# Driver_control.net
KiCad netlist of a schematic drawn in EAGLE
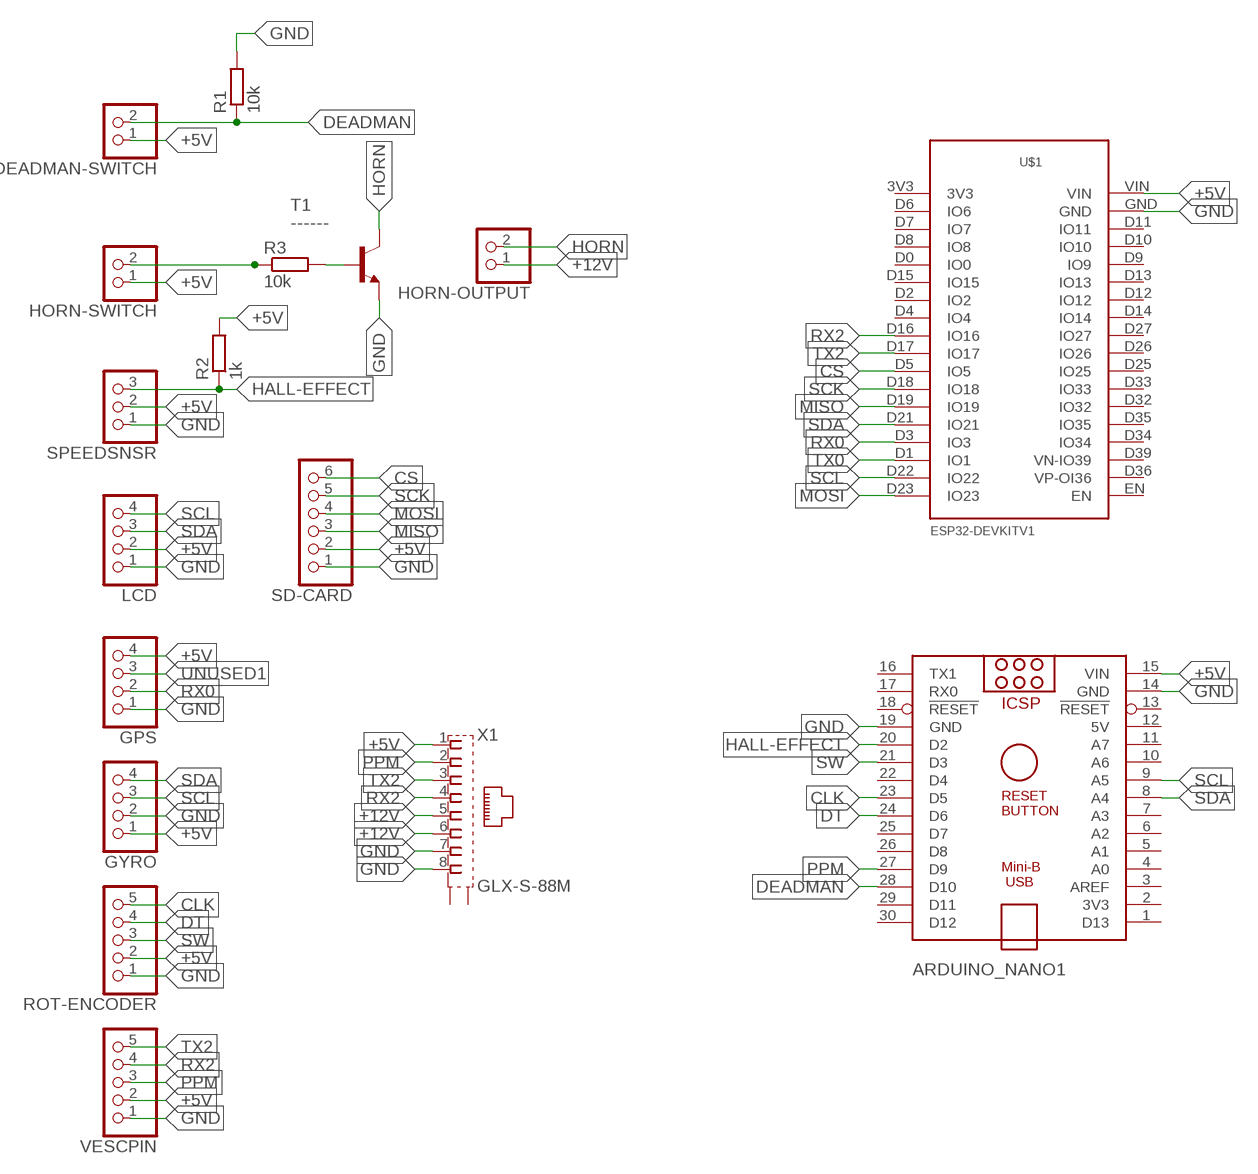
[diagram p0: schematic, sheet 1]

(export (version "E")
  (design (tool "Eeschema 10.0.6"))
  (components
    (comp (ref "ARDUINO_NANO1")
      (value "ARDUINO_NANO")
      (footprint "eagle-import:ARDUINO_NANO")
      (libsource (lib "eagle-import") (part "ARDUINO_NANO"))
    )
    (comp (ref "DEADMAN-SWITCH")
      (value "PINHD-1X2")
      (footprint "eagle-import:1X02")
      (libsource (lib "eagle-import") (part "PINHD-1X2"))
    )
    (comp (ref "GPS")
      (value "PINHD-1X4")
      (footprint "eagle-import:1X04")
      (libsource (lib "eagle-import") (part "PINHD-1X4"))
    )
    (comp (ref "GYRO")
      (value "PINHD-1X4")
      (footprint "eagle-import:1X04")
      (libsource (lib "eagle-import") (part "PINHD-1X4"))
    )
    (comp (ref "HORN-OUTPUT")
      (value "PINHD-1X2")
      (footprint "eagle-import:1X02")
      (libsource (lib "eagle-import") (part "PINHD-1X2"))
    )
    (comp (ref "HORN-SWITCH")
      (value "PINHD-1X2")
      (footprint "eagle-import:1X02")
      (libsource (lib "eagle-import") (part "PINHD-1X2"))
    )
    (comp (ref "LCD")
      (value "PINHD-1X4")
      (footprint "eagle-import:1X04")
      (libsource (lib "eagle-import") (part "PINHD-1X4"))
    )
    (comp (ref "R1")
      (value "10k")
      (footprint "eagle-import:0204_7")
      (libsource (lib "eagle-import") (part "R-EU_0204/7"))
    )
    (comp (ref "R2")
      (value "1k")
      (footprint "eagle-import:0204_7")
      (libsource (lib "eagle-import") (part "R-EU_0204/7"))
    )
    (comp (ref "R3")
      (value "10k")
      (footprint "eagle-import:0204_7")
      (libsource (lib "eagle-import") (part "R-EU_0204/7"))
    )
    (comp (ref "ROT-ENCODER")
      (value "PINHD-1X5")
      (footprint "eagle-import:1X05")
      (libsource (lib "eagle-import") (part "PINHD-1X5"))
    )
    (comp (ref "SD-CARD")
      (value "PINHD-1X6")
      (footprint "eagle-import:1X06")
      (libsource (lib "eagle-import") (part "PINHD-1X6"))
    )
    (comp (ref "SPEEDSNSR")
      (value "PINHD-1X3")
      (footprint "eagle-import:1X03")
      (libsource (lib "eagle-import") (part "PINHD-1X3"))
    )
    (comp (ref "T1")
      (value "------")
      (footprint "eagle-import:TO5")
      (libsource (lib "eagle-import") (part "2N2219"))
    )
    (comp (ref "U$1")
      (value "ESP32DEVKITV1")
      (footprint "eagle-import:ESP32-DEVKITV1")
      (libsource (lib "eagle-import") (part "ESP32DEVKITV1"))
    )
    (comp (ref "VESCPIN")
      (value "PINHD-1X5")
      (footprint "eagle-import:1X05")
      (libsource (lib "eagle-import") (part "PINHD-1X5"))
    )
    (comp (ref "X1")
      (value "GLX-S-88M")
      (footprint "eagle-import:GLX-S-88M")
      (libsource (lib "eagle-import") (part "GLX-S-88M"))
    )
  )
  (nets
    (net (code "1") (name "+5V") (class "Default")
      (node (ref "ARDUINO_NANO1") (pin "15") (pinfunction "VIN_15") (pintype "power_in"))
      (node (ref "DEADMAN-SWITCH") (pin "1") (pinfunction "1_1") (pintype "passive"))
      (node (ref "GPS") (pin "4") (pinfunction "4_4") (pintype "passive"))
      (node (ref "GYRO") (pin "1") (pinfunction "1_1") (pintype "passive"))
      (node (ref "HORN-SWITCH") (pin "1") (pinfunction "1_1") (pintype "passive"))
      (node (ref "LCD") (pin "2") (pinfunction "2_2") (pintype "passive"))
      (node (ref "R2") (pin "2") (pinfunction "2_2") (pintype "passive"))
      (node (ref "ROT-ENCODER") (pin "2") (pinfunction "2_2") (pintype "passive"))
      (node (ref "SD-CARD") (pin "2") (pinfunction "2_2") (pintype "passive"))
      (node (ref "SPEEDSNSR") (pin "2") (pinfunction "2_2") (pintype "passive"))
      (node (ref "U$1") (pin "VIN") (pinfunction "VIN_VIN") (pintype "bidirectional"))
      (node (ref "VESCPIN") (pin "2") (pinfunction "2_2") (pintype "passive"))
      (node (ref "X1") (pin "1") (pinfunction "1_1") (pintype "passive"))
    )
    (net (code "2") (name "+12V") (class "Default")
      (node (ref "HORN-OUTPUT") (pin "1") (pinfunction "1_1") (pintype "passive"))
      (node (ref "X1") (pin "5") (pinfunction "5_5") (pintype "passive"))
      (node (ref "X1") (pin "6") (pinfunction "6_6") (pintype "passive"))
    )
    (net (code "3") (name "/5V") (class "Default")
      (node (ref "ARDUINO_NANO1") (pin "12") (pinfunction "5V_12") (pintype "power_in"))
    )
    (net (code "4") (name "CLK") (class "Default")
      (node (ref "ARDUINO_NANO1") (pin "23") (pinfunction "D5_23") (pintype "bidirectional"))
      (node (ref "ROT-ENCODER") (pin "5") (pinfunction "5_5") (pintype "passive"))
    )
    (net (code "5") (name "CS") (class "Default")
      (node (ref "SD-CARD") (pin "6") (pinfunction "6_6") (pintype "passive"))
      (node (ref "U$1") (pin "D5") (pinfunction "IO5_D5") (pintype "bidirectional"))
    )
    (net (code "6") (name "DEADMAN") (class "Default")
      (node (ref "ARDUINO_NANO1") (pin "28") (pinfunction "D10_28") (pintype "bidirectional"))
      (node (ref "DEADMAN-SWITCH") (pin "2") (pinfunction "2_2") (pintype "passive"))
      (node (ref "R1") (pin "1") (pinfunction "1_1") (pintype "passive"))
    )
    (net (code "7") (name "DT") (class "Default")
      (node (ref "ARDUINO_NANO1") (pin "24") (pinfunction "D6_24") (pintype "bidirectional"))
      (node (ref "ROT-ENCODER") (pin "4") (pinfunction "4_4") (pintype "passive"))
    )
    (net (code "8") (name "GND") (class "Default")
      (node (ref "ARDUINO_NANO1") (pin "14") (pinfunction "GND_14") (pintype "power_in"))
      (node (ref "ARDUINO_NANO1") (pin "19") (pinfunction "GND_19") (pintype "power_in"))
      (node (ref "GPS") (pin "1") (pinfunction "1_1") (pintype "passive"))
      (node (ref "GYRO") (pin "2") (pinfunction "2_2") (pintype "passive"))
      (node (ref "LCD") (pin "1") (pinfunction "1_1") (pintype "passive"))
      (node (ref "R1") (pin "2") (pinfunction "2_2") (pintype "passive"))
      (node (ref "ROT-ENCODER") (pin "1") (pinfunction "1_1") (pintype "passive"))
      (node (ref "SD-CARD") (pin "1") (pinfunction "1_1") (pintype "passive"))
      (node (ref "SPEEDSNSR") (pin "1") (pinfunction "1_1") (pintype "passive"))
      (node (ref "T1") (pin "1") (pinfunction "E_1") (pintype "passive"))
      (node (ref "U$1") (pin "GND") (pinfunction "GND_GND") (pintype "bidirectional"))
      (node (ref "VESCPIN") (pin "1") (pinfunction "1_1") (pintype "passive"))
      (node (ref "X1") (pin "7") (pinfunction "7_7") (pintype "passive"))
      (node (ref "X1") (pin "8") (pinfunction "8_8") (pintype "passive"))
    )
    (net (code "9") (name "HALL-EFFECT") (class "Default")
      (node (ref "ARDUINO_NANO1") (pin "20") (pinfunction "D2_20") (pintype "bidirectional"))
      (node (ref "R2") (pin "1") (pinfunction "1_1") (pintype "passive"))
      (node (ref "SPEEDSNSR") (pin "3") (pinfunction "3_3") (pintype "passive"))
    )
    (net (code "10") (name "HORN") (class "Default")
      (node (ref "HORN-OUTPUT") (pin "2") (pinfunction "2_2") (pintype "passive"))
      (node (ref "T1") (pin "3") (pinfunction "C_3") (pintype "passive"))
    )
    (net (code "11") (name "MISO") (class "Default")
      (node (ref "SD-CARD") (pin "3") (pinfunction "3_3") (pintype "passive"))
      (node (ref "U$1") (pin "D19") (pinfunction "IO19_D19") (pintype "bidirectional"))
    )
    (net (code "12") (name "MOSI") (class "Default")
      (node (ref "SD-CARD") (pin "4") (pinfunction "4_4") (pintype "passive"))
      (node (ref "U$1") (pin "D23") (pinfunction "IO23_D23") (pintype "bidirectional"))
    )
    (net (code "13") (name "Net-(HORN-SWITCH-Pad2)") (class "Default")
      (node (ref "HORN-SWITCH") (pin "2") (pinfunction "2_2") (pintype "passive"))
      (node (ref "R3") (pin "1") (pinfunction "1_1") (pintype "passive"))
    )
    (net (code "14") (name "Net-(T1-B)") (class "Default")
      (node (ref "R3") (pin "2") (pinfunction "2_2") (pintype "passive"))
      (node (ref "T1") (pin "2") (pinfunction "B_2") (pintype "passive"))
    )
    (net (code "15") (name "PPM") (class "Default")
      (node (ref "ARDUINO_NANO1") (pin "27") (pinfunction "D9_27") (pintype "bidirectional"))
      (node (ref "VESCPIN") (pin "3") (pinfunction "3_3") (pintype "passive"))
      (node (ref "X1") (pin "2") (pinfunction "2_2") (pintype "passive"))
    )
    (net (code "16") (name "RX0") (class "Default")
      (node (ref "GPS") (pin "2") (pinfunction "2_2") (pintype "passive"))
      (node (ref "U$1") (pin "D3") (pinfunction "IO3_D3") (pintype "bidirectional"))
    )
    (net (code "17") (name "RX2") (class "Default")
      (node (ref "U$1") (pin "D16") (pinfunction "IO16_D16") (pintype "bidirectional"))
      (node (ref "VESCPIN") (pin "4") (pinfunction "4_4") (pintype "passive"))
      (node (ref "X1") (pin "4") (pinfunction "4_4") (pintype "passive"))
    )
    (net (code "18") (name "SCK") (class "Default")
      (node (ref "SD-CARD") (pin "5") (pinfunction "5_5") (pintype "passive"))
      (node (ref "U$1") (pin "D18") (pinfunction "IO18_D18") (pintype "bidirectional"))
    )
    (net (code "19") (name "SCL") (class "Default")
      (node (ref "ARDUINO_NANO1") (pin "9") (pinfunction "A5_9") (pintype "bidirectional"))
      (node (ref "GYRO") (pin "3") (pinfunction "3_3") (pintype "passive"))
      (node (ref "LCD") (pin "4") (pinfunction "4_4") (pintype "passive"))
      (node (ref "U$1") (pin "D22") (pinfunction "IO22_D22") (pintype "bidirectional"))
    )
    (net (code "20") (name "SDA") (class "Default")
      (node (ref "ARDUINO_NANO1") (pin "8") (pinfunction "A4_8") (pintype "bidirectional"))
      (node (ref "GYRO") (pin "4") (pinfunction "4_4") (pintype "passive"))
      (node (ref "LCD") (pin "3") (pinfunction "3_3") (pintype "passive"))
      (node (ref "U$1") (pin "D21") (pinfunction "IO21_D21") (pintype "bidirectional"))
    )
    (net (code "21") (name "SW") (class "Default")
      (node (ref "ARDUINO_NANO1") (pin "21") (pinfunction "D3_21") (pintype "bidirectional"))
      (node (ref "ROT-ENCODER") (pin "3") (pinfunction "3_3") (pintype "passive"))
    )
    (net (code "22") (name "TX0") (class "Default")
      (node (ref "U$1") (pin "D1") (pinfunction "IO1_D1") (pintype "bidirectional"))
    )
    (net (code "23") (name "TX2") (class "Default")
      (node (ref "U$1") (pin "D17") (pinfunction "IO17_D17") (pintype "bidirectional"))
      (node (ref "VESCPIN") (pin "5") (pinfunction "5_5") (pintype "passive"))
      (node (ref "X1") (pin "3") (pinfunction "3_3") (pintype "passive"))
    )
    (net (code "24") (name "UNUSED1") (class "Default")
      (node (ref "GPS") (pin "3") (pinfunction "3_3") (pintype "passive"))
    )
    (net (code "25") (name "unconnected-(ARDUINO_NANO1-3V3-Pad2)") (class "Default")
      (node (ref "ARDUINO_NANO1") (pin "2") (pinfunction "3V3_2") (pintype "output"))
    )
    (net (code "26") (name "unconnected-(ARDUINO_NANO1-A0-Pad4)") (class "Default")
      (node (ref "ARDUINO_NANO1") (pin "4") (pinfunction "A0_4") (pintype "bidirectional"))
    )
    (net (code "27") (name "unconnected-(ARDUINO_NANO1-A1-Pad5)") (class "Default")
      (node (ref "ARDUINO_NANO1") (pin "5") (pinfunction "A1_5") (pintype "bidirectional"))
    )
    (net (code "28") (name "unconnected-(ARDUINO_NANO1-A2-Pad6)") (class "Default")
      (node (ref "ARDUINO_NANO1") (pin "6") (pinfunction "A2_6") (pintype "bidirectional"))
    )
    (net (code "29") (name "unconnected-(ARDUINO_NANO1-A3-Pad7)") (class "Default")
      (node (ref "ARDUINO_NANO1") (pin "7") (pinfunction "A3_7") (pintype "bidirectional"))
    )
    (net (code "30") (name "unconnected-(ARDUINO_NANO1-A6-Pad10)") (class "Default")
      (node (ref "ARDUINO_NANO1") (pin "10") (pinfunction "A6_10") (pintype "bidirectional"))
    )
    (net (code "31") (name "unconnected-(ARDUINO_NANO1-A7-Pad11)") (class "Default")
      (node (ref "ARDUINO_NANO1") (pin "11") (pinfunction "A7_11") (pintype "bidirectional"))
    )
    (net (code "32") (name "unconnected-(ARDUINO_NANO1-AREF-Pad3)") (class "Default")
      (node (ref "ARDUINO_NANO1") (pin "3") (pinfunction "AREF_3") (pintype "input"))
    )
    (net (code "33") (name "unconnected-(ARDUINO_NANO1-D4-Pad22)") (class "Default")
      (node (ref "ARDUINO_NANO1") (pin "22") (pinfunction "D4_22") (pintype "bidirectional"))
    )
    (net (code "34") (name "unconnected-(ARDUINO_NANO1-D7-Pad25)") (class "Default")
      (node (ref "ARDUINO_NANO1") (pin "25") (pinfunction "D7_25") (pintype "bidirectional"))
    )
    (net (code "35") (name "unconnected-(ARDUINO_NANO1-D8-Pad26)") (class "Default")
      (node (ref "ARDUINO_NANO1") (pin "26") (pinfunction "D8_26") (pintype "bidirectional"))
    )
    (net (code "36") (name "unconnected-(ARDUINO_NANO1-D11-Pad29)") (class "Default")
      (node (ref "ARDUINO_NANO1") (pin "29") (pinfunction "D11_29") (pintype "bidirectional"))
    )
    (net (code "37") (name "unconnected-(ARDUINO_NANO1-D12-Pad30)") (class "Default")
      (node (ref "ARDUINO_NANO1") (pin "30") (pinfunction "D12_30") (pintype "bidirectional"))
    )
    (net (code "38") (name "unconnected-(ARDUINO_NANO1-D13-Pad1)") (class "Default")
      (node (ref "ARDUINO_NANO1") (pin "1") (pinfunction "D13_1") (pintype "bidirectional"))
    )
    (net (code "39") (name "unconnected-(ARDUINO_NANO1-RX0-Pad17)") (class "Default")
      (node (ref "ARDUINO_NANO1") (pin "17") (pinfunction "RX0_17") (pintype "bidirectional"))
    )
    (net (code "40") (name "unconnected-(ARDUINO_NANO1-TX1-Pad16)") (class "Default")
      (node (ref "ARDUINO_NANO1") (pin "16") (pinfunction "TX1_16") (pintype "bidirectional"))
    )
    (net (code "41") (name "unconnected-(ARDUINO_NANO1-~{RESET}-Pad13)") (class "Default")
      (node (ref "ARDUINO_NANO1") (pin "13") (pinfunction "~{RESET}_13") (pintype "input"))
    )
    (net (code "42") (name "unconnected-(ARDUINO_NANO1-~{RESET}-Pad18)") (class "Default")
      (node (ref "ARDUINO_NANO1") (pin "18") (pinfunction "~{RESET}_18") (pintype "input"))
    )
    (net (code "43") (name "unconnected-(U$1-IO0-PadD0)") (class "Default")
      (node (ref "U$1") (pin "D0") (pinfunction "IO0_D0") (pintype "bidirectional"))
    )
    (net (code "44") (name "unconnected-(U$1-IO2-PadD2)") (class "Default")
      (node (ref "U$1") (pin "D2") (pinfunction "IO2_D2") (pintype "bidirectional"))
    )
    (net (code "45") (name "unconnected-(U$1-IO4-PadD4)") (class "Default")
      (node (ref "U$1") (pin "D4") (pinfunction "IO4_D4") (pintype "bidirectional"))
    )
    (net (code "46") (name "unconnected-(U$1-IO6-PadD6)") (class "Default")
      (node (ref "U$1") (pin "D6") (pinfunction "IO6_D6") (pintype "bidirectional"))
    )
    (net (code "47") (name "unconnected-(U$1-IO7-PadD7)") (class "Default")
      (node (ref "U$1") (pin "D7") (pinfunction "IO7_D7") (pintype "bidirectional"))
    )
    (net (code "48") (name "unconnected-(U$1-IO8-PadD8)") (class "Default")
      (node (ref "U$1") (pin "D8") (pinfunction "IO8_D8") (pintype "bidirectional"))
    )
    (net (code "49") (name "unconnected-(U$1-IO9-PadD9)") (class "Default")
      (node (ref "U$1") (pin "D9") (pinfunction "IO9_D9") (pintype "bidirectional"))
    )
    (net (code "50") (name "unconnected-(U$1-IO10-PadD10)") (class "Default")
      (node (ref "U$1") (pin "D10") (pinfunction "IO10_D10") (pintype "bidirectional"))
    )
    (net (code "51") (name "unconnected-(U$1-IO11-PadD11)") (class "Default")
      (node (ref "U$1") (pin "D11") (pinfunction "IO11_D11") (pintype "bidirectional"))
    )
    (net (code "52") (name "unconnected-(U$1-IO12-PadD12)") (class "Default")
      (node (ref "U$1") (pin "D12") (pinfunction "IO12_D12") (pintype "bidirectional"))
    )
    (net (code "53") (name "unconnected-(U$1-IO13-PadD13)") (class "Default")
      (node (ref "U$1") (pin "D13") (pinfunction "IO13_D13") (pintype "bidirectional"))
    )
    (net (code "54") (name "unconnected-(U$1-IO14-PadD14)") (class "Default")
      (node (ref "U$1") (pin "D14") (pinfunction "IO14_D14") (pintype "bidirectional"))
    )
    (net (code "55") (name "unconnected-(U$1-IO15-PadD15)") (class "Default")
      (node (ref "U$1") (pin "D15") (pinfunction "IO15_D15") (pintype "bidirectional"))
    )
    (net (code "56") (name "unconnected-(U$1-IO25-PadD25)") (class "Default")
      (node (ref "U$1") (pin "D25") (pinfunction "IO25_D25") (pintype "bidirectional"))
    )
    (net (code "57") (name "unconnected-(U$1-IO26-PadD26)") (class "Default")
      (node (ref "U$1") (pin "D26") (pinfunction "IO26_D26") (pintype "bidirectional"))
    )
    (net (code "58") (name "unconnected-(U$1-IO27-PadD27)") (class "Default")
      (node (ref "U$1") (pin "D27") (pinfunction "IO27_D27") (pintype "bidirectional"))
    )
    (net (code "59") (name "unconnected-(U$1-IO32-PadD32)") (class "Default")
      (node (ref "U$1") (pin "D32") (pinfunction "IO32_D32") (pintype "bidirectional"))
    )
    (net (code "60") (name "unconnected-(U$1-IO33-PadD33)") (class "Default")
      (node (ref "U$1") (pin "D33") (pinfunction "IO33_D33") (pintype "bidirectional"))
    )
    (net (code "61") (name "unconnected-(U$1-IO34-PadD34)") (class "Default")
      (node (ref "U$1") (pin "D34") (pinfunction "IO34_D34") (pintype "bidirectional"))
    )
    (net (code "62") (name "unconnected-(U$1-IO35-PadD35)") (class "Default")
      (node (ref "U$1") (pin "D35") (pinfunction "IO35_D35") (pintype "bidirectional"))
    )
    (net (code "63") (name "unconnected-(U$1-Pad3V3)") (class "Default")
      (node (ref "U$1") (pin "3V3") (pinfunction "3V3_3V3") (pintype "bidirectional"))
    )
    (net (code "64") (name "unconnected-(U$1-PadEN)") (class "Default")
      (node (ref "U$1") (pin "EN") (pinfunction "EN_EN") (pintype "bidirectional"))
    )
    (net (code "65") (name "unconnected-(U$1-VN-IO39-PadD39)") (class "Default")
      (node (ref "U$1") (pin "D39") (pinfunction "VN-IO39_D39") (pintype "bidirectional"))
    )
    (net (code "66") (name "unconnected-(U$1-VP-OI36-PadD36)") (class "Default")
      (node (ref "U$1") (pin "D36") (pinfunction "VP-OI36_D36") (pintype "bidirectional"))
    )
    (net (code "67") (name "unconnected-(X1-PadS1)") (class "Default")
      (node (ref "X1") (pin "S1") (pinfunction "S1_S1") (pintype "passive"))
    )
    (net (code "68") (name "unconnected-(X1-PadS2)") (class "Default")
      (node (ref "X1") (pin "S2") (pinfunction "S2_S2") (pintype "passive"))
    )
  )
)
